# Master_Micro_Controller.net
KiCad netlist of a schematic drawn in Altium Designer
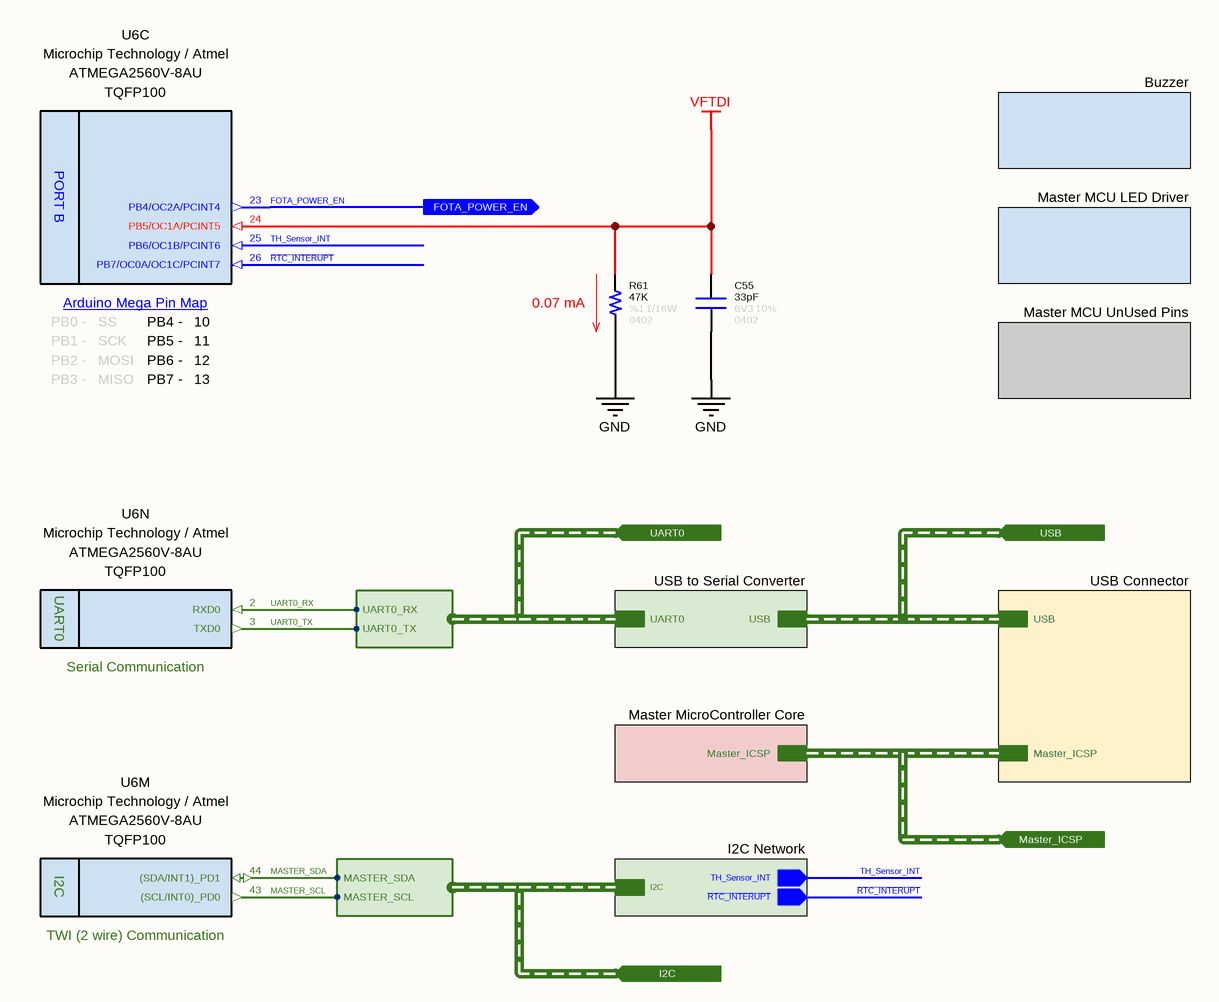
[diagram p0: Master Micro Controller.SchDoc]

(export (version "E")
  (design (tool "Eeschema 10.0.6"))
  (components
    (comp (ref "C55")
      (value "33pF")
      (footprint "CAPACITOR_0402")
      (description "Capacitor - 33pF [0402] (Ceramic)")
      (fields
        (field (name "MANUFACTURER PART NUMBER") "C0402C330J9RACAUTO")
        (field (name "TOLERANCE") "10%")
        (field (name "CASE") "0402")
        (field (name "VOLTAGE") "6V3")
      )
      (libsource (lib "P101DA_Library") (part "Capacitor - 33pF [0402-6V3]"))
    )
    (comp (ref "R61")
      (value "47K")
      (footprint "RESISTOR_0402")
      (description "Thick Film Resistors - SMD 1/16 W 47 KOhm 1%")
      (fields
        (field (name "MANUFACTURER PART NUMBER") "CRCW040247K0FKED")
        (field (name "TOLERANCE") "%1")
        (field (name "CASE") "0402")
        (field (name "POWER") "1/16W")
        (field (name "Comment") "47K - 0402 - %1 - 1/16W")
      )
      (libsource (lib "P101DA_Library") (part "Resistor - 47K [0402]"))
    )
    (comp (ref "U6")
      (value "ATMEGA2560V-8AU")
      (footprint "TQFP-100")
      (description "ATmega Series 256 KB Flash 8 KB SRAM 8 MHz 8-Bit Microcontroller - TQFP-100")
      (fields
        (field (name "MANUFACTURER NAME") "Microchip Technology / Atmel")
        (field (name "MANUFACTURER PART NUMBER") "ATMEGA2560V-8AU")
        (field (name "CASE") "TQFP100")
      )
      (libsource (lib "P101DA_Library") (part "IC - AtMega2560V-8AU"))
    )
  )
  (nets
    (net (code "5") (name "/FOTA_POWER_EN") (class "Default")
      (node (ref "U6") (pin "23") (pinfunction "PB4/OC2A/PCINT4_23") (pintype "output"))
    )
    (net (code "6") (name "/MASTER_SCL") (class "Default")
      (node (ref "U6") (pin "43") (pinfunction "(SCL/INT0)_PD0_43") (pintype "output"))
    )
    (net (code "7") (name "/MASTER_SDA") (class "Default")
      (node (ref "U6") (pin "44") (pinfunction "(SDA/INT1)_PD1_44") (pintype "bidirectional"))
    )
    (net (code "9") (name "/TH_Sensor_INT") (class "Default")
      (node (ref "U6") (pin "25") (pinfunction "PB6/OC1B/PCINT6_25") (pintype "input"))
    )
    (net (code "10") (name "/UART0_RX") (class "Default")
      (node (ref "U6") (pin "2") (pinfunction "RXD0_2") (pintype "input"))
    )
    (net (code "11") (name "/UART0_TX") (class "Default")
      (node (ref "U6") (pin "3") (pinfunction "TXD0_3") (pintype "output"))
    )
    (net (code "15") (name "/~{RTC_INTERUPT}") (class "Default")
      (node (ref "U6") (pin "26") (pinfunction "PB7/OC0A/OC1C/PCINT7_26") (pintype "input"))
    )
    (net (code "16") (name "GND") (class "Default")
      (node (ref "C55") (pin "1") (pinfunction "1_1") (pintype "passive"))
      (node (ref "R61") (pin "1") (pinfunction "1_1") (pintype "passive"))
    )
    (net (code "17") (name "VFTDI") (class "Default")
      (node (ref "C55") (pin "2") (pinfunction "2_2") (pintype "passive"))
      (node (ref "R61") (pin "2") (pinfunction "2_2") (pintype "passive"))
      (node (ref "U6") (pin "24") (pinfunction "PB5/OC1A/PCINT5_24") (pintype "input"))
    )
  )
)
